# PWM_CON_USB.net
KiCad netlist of a schematic drawn in Altium Designer
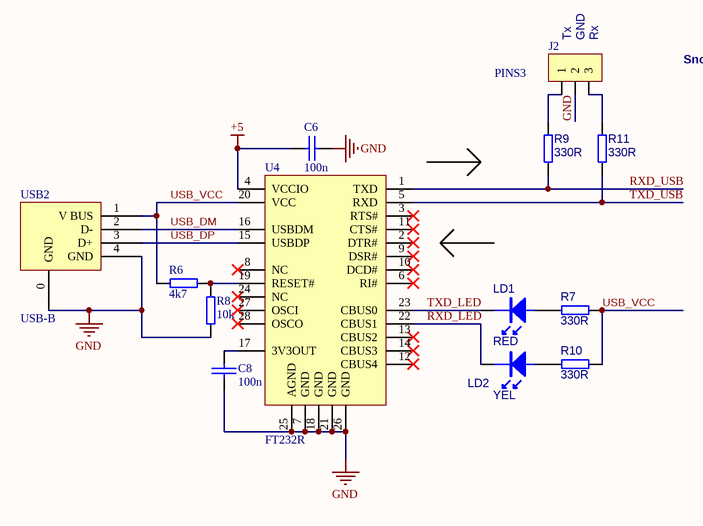
[diagram p0: PWM_CON_USB.SchDoc]

(export (version "E")
  (design (tool "Eeschema 10.0.6"))
  (components
    (comp (ref "C6")
      (value "100n")
      (footprint "0603")
      (fields (field (name "PARTNO") "R8835"))
      (libsource (lib "*") (part "CAP"))
    )
    (comp (ref "C8")
      (value "100n")
      (footprint "0603")
      (fields (field (name "PARTNO") "R8835"))
      (libsource (lib "*") (part "CAP"))
    )
    (comp (ref "J2")
      (value "PINS3")
      (footprint "SIP3")
      (fields (field (name "PARTNO") "P5430"))
      (libsource (lib "DEVICE") (part "CON3"))
    )
    (comp (ref "LD1")
      (value "RED")
      (footprint "0805DIODE")
      (fields (field (name "PARTNO") "Y1107"))
      (libsource (lib "*") (part "LED"))
    )
    (comp (ref "LD2")
      (value "YEL")
      (footprint "0805DIODE")
      (fields (field (name "PARTNO") "Y1116"))
      (libsource (lib "*") (part "LED"))
    )
    (comp (ref "R6")
      (value "4k7")
      (footprint "0603")
      (description "1% Resistor")
      (fields (field (name "PARTNO") "R1644"))
      (libsource (lib "DEVICE") (part "RES8"))
    )
    (comp (ref "R7")
      (value "330R")
      (footprint "0603")
      (fields (field (name "PARTNO") "R1560"))
      (libsource (lib "DEVICE") (part "RES8"))
    )
    (comp (ref "R8")
      (value "10k")
      (footprint "0603")
      (description "1% Resistor")
      (fields (field (name "PARTNO") "R1668"))
      (libsource (lib "DEVICE") (part "RES8"))
    )
    (comp (ref "R9")
      (value "330R")
      (footprint "0603")
      (fields (field (name "PARTNO") "R1560"))
      (libsource (lib "DEVICE") (part "RES8"))
    )
    (comp (ref "R10")
      (value "330R")
      (footprint "0603")
      (fields (field (name "PARTNO") "R1560"))
      (libsource (lib "DEVICE") (part "RES8"))
    )
    (comp (ref "R11")
      (value "330R")
      (footprint "0603")
      (fields (field (name "PARTNO") "R1560"))
      (libsource (lib "DEVICE") (part "RES8"))
    )
    (comp (ref "U4")
      (value "FT232R")
      (footprint "ssop28")
      (description "FTDI USB - USART")
      (fields (field (name "PARTNO") "1146032RL"))
      (libsource (lib "FTDI") (part "FT232R"))
    )
    (comp (ref "USB2")
      (value "USB-B")
      (footprint "USB_BV")
      (fields (field (name "PARTNO") "1177884"))
      (libsource (lib "DEVICE") (part "USB-B"))
    )
  )
  (nets
    (net (code "1") (name "+5") (class "Default")
      (node (ref "C6") (pin "2") (pintype "passive"))
      (node (ref "U4") (pin "4") (pinfunction "VCCIO_4") (pintype "passive"))
    )
    (net (code "2") (name "/RXD_LED") (class "Default")
      (node (ref "LD2") (pin "K") (pintype "passive"))
      (node (ref "U4") (pin "22") (pinfunction "CBUS1_22") (pintype "passive"))
    )
    (net (code "3") (name "/RXD_USB") (class "Default")
      (node (ref "R9") (pin "2") (pintype "passive"))
      (node (ref "U4") (pin "1") (pinfunction "TXD_1") (pintype "passive"))
    )
    (net (code "4") (name "/TXD_LED") (class "Default")
      (node (ref "LD1") (pin "K") (pintype "passive"))
      (node (ref "U4") (pin "23") (pinfunction "CBUS0_23") (pintype "passive"))
    )
    (net (code "5") (name "/TXD_USB") (class "Default")
      (node (ref "R11") (pin "2") (pintype "passive"))
      (node (ref "U4") (pin "5") (pinfunction "RXD_5") (pintype "passive"))
    )
    (net (code "6") (name "/USB_DM") (class "Default")
      (node (ref "U4") (pin "16") (pinfunction "USBDM_16") (pintype "passive"))
      (node (ref "USB2") (pin "2") (pinfunction "D-_2") (pintype "passive"))
    )
    (net (code "7") (name "/USB_DP") (class "Default")
      (node (ref "U4") (pin "15") (pinfunction "USBDP_15") (pintype "passive"))
      (node (ref "USB2") (pin "3") (pinfunction "D+_3") (pintype "passive"))
    )
    (net (code "8") (name "/USB_VCC") (class "Default")
      (node (ref "R10") (pin "1") (pintype "passive"))
      (node (ref "R6") (pin "1") (pintype "passive"))
      (node (ref "R7") (pin "1") (pintype "passive"))
      (node (ref "U4") (pin "20") (pinfunction "VCC_20") (pintype "passive"))
      (node (ref "USB2") (pin "1") (pinfunction "V_BUS_1") (pintype "passive"))
    )
    (net (code "9") (name "GND") (class "Default")
      (node (ref "C6") (pin "1") (pintype "passive"))
      (node (ref "C8") (pin "1") (pintype "passive"))
      (node (ref "J2") (pin "2") (pinfunction "2_2") (pintype "passive"))
      (node (ref "R8") (pin "1") (pintype "passive"))
      (node (ref "U4") (pin "18") (pinfunction "GND_18") (pintype "passive"))
      (node (ref "U4") (pin "21") (pinfunction "GND_21") (pintype "passive"))
      (node (ref "U4") (pin "25") (pinfunction "AGND_25") (pintype "passive"))
      (node (ref "U4") (pin "26") (pinfunction "GND_26") (pintype "passive"))
      (node (ref "U4") (pin "7") (pinfunction "GND_7") (pintype "passive"))
      (node (ref "USB2") (pin "0") (pinfunction "GND_0") (pintype "power_in"))
      (node (ref "USB2") (pin "4") (pinfunction "GND_4") (pintype "passive"))
    )
    (net (code "10") (name "Net-(J2-Pad1)") (class "Default")
      (node (ref "J2") (pin "1") (pinfunction "1_1") (pintype "passive"))
      (node (ref "R9") (pin "1") (pintype "passive"))
    )
    (net (code "11") (name "Net-(J2-Pad3)") (class "Default")
      (node (ref "J2") (pin "3") (pinfunction "3_3") (pintype "passive"))
      (node (ref "R11") (pin "1") (pintype "passive"))
    )
    (net (code "12") (name "Net-(LD1-PadA)") (class "Default")
      (node (ref "LD1") (pin "A") (pintype "passive"))
      (node (ref "R7") (pin "2") (pintype "passive"))
    )
    (net (code "13") (name "Net-(LD2-PadA)") (class "Default")
      (node (ref "LD2") (pin "A") (pintype "passive"))
      (node (ref "R10") (pin "2") (pintype "passive"))
    )
    (net (code "14") (name "Net-(U4-3V3OUT)") (class "Default")
      (node (ref "C8") (pin "2") (pintype "passive"))
      (node (ref "U4") (pin "17") (pinfunction "3V3OUT_17") (pintype "passive"))
    )
    (net (code "15") (name "Net-(U4-RESET#)") (class "Default")
      (node (ref "R6") (pin "2") (pintype "passive"))
      (node (ref "R8") (pin "2") (pintype "passive"))
      (node (ref "U4") (pin "19") (pinfunction "RESET#_19") (pintype "passive"))
    )
    (net (code "16") (name "unconnected-(U4-CBUS2-Pad13)") (class "Default")
      (node (ref "U4") (pin "13") (pinfunction "CBUS2_13") (pintype "passive+no_connect"))
    )
    (net (code "17") (name "unconnected-(U4-CBUS3-Pad14)") (class "Default")
      (node (ref "U4") (pin "14") (pinfunction "CBUS3_14") (pintype "passive+no_connect"))
    )
    (net (code "18") (name "unconnected-(U4-CBUS4-Pad12)") (class "Default")
      (node (ref "U4") (pin "12") (pinfunction "CBUS4_12") (pintype "passive+no_connect"))
    )
    (net (code "19") (name "unconnected-(U4-CTS#-Pad11)") (class "Default")
      (node (ref "U4") (pin "11") (pinfunction "CTS#_11") (pintype "passive+no_connect"))
    )
    (net (code "20") (name "unconnected-(U4-DCD#-Pad10)") (class "Default")
      (node (ref "U4") (pin "10") (pinfunction "DCD#_10") (pintype "passive+no_connect"))
    )
    (net (code "21") (name "unconnected-(U4-DSR#-Pad9)") (class "Default")
      (node (ref "U4") (pin "9") (pinfunction "DSR#_9") (pintype "passive+no_connect"))
    )
    (net (code "22") (name "unconnected-(U4-DTR#-Pad2)") (class "Default")
      (node (ref "U4") (pin "2") (pinfunction "DTR#_2") (pintype "passive+no_connect"))
    )
    (net (code "23") (name "unconnected-(U4-NC-Pad8)") (class "Default")
      (node (ref "U4") (pin "8") (pinfunction "NC_8") (pintype "passive+no_connect"))
    )
    (net (code "24") (name "unconnected-(U4-NC-Pad24)") (class "Default")
      (node (ref "U4") (pin "24") (pinfunction "NC_24") (pintype "passive+no_connect"))
    )
    (net (code "25") (name "unconnected-(U4-OSCI-Pad27)") (class "Default")
      (node (ref "U4") (pin "27") (pinfunction "OSCI_27") (pintype "passive+no_connect"))
    )
    (net (code "26") (name "unconnected-(U4-OSCO-Pad28)") (class "Default")
      (node (ref "U4") (pin "28") (pinfunction "OSCO_28") (pintype "passive+no_connect"))
    )
    (net (code "27") (name "unconnected-(U4-RI#-Pad6)") (class "Default")
      (node (ref "U4") (pin "6") (pinfunction "RI#_6") (pintype "passive+no_connect"))
    )
    (net (code "28") (name "unconnected-(U4-RTS#-Pad3)") (class "Default")
      (node (ref "U4") (pin "3") (pinfunction "RTS#_3") (pintype "passive+no_connect"))
    )
  )
)
